# EASY_EDA_File.net
KiCad netlist of a schematic drawn in EasyEDA
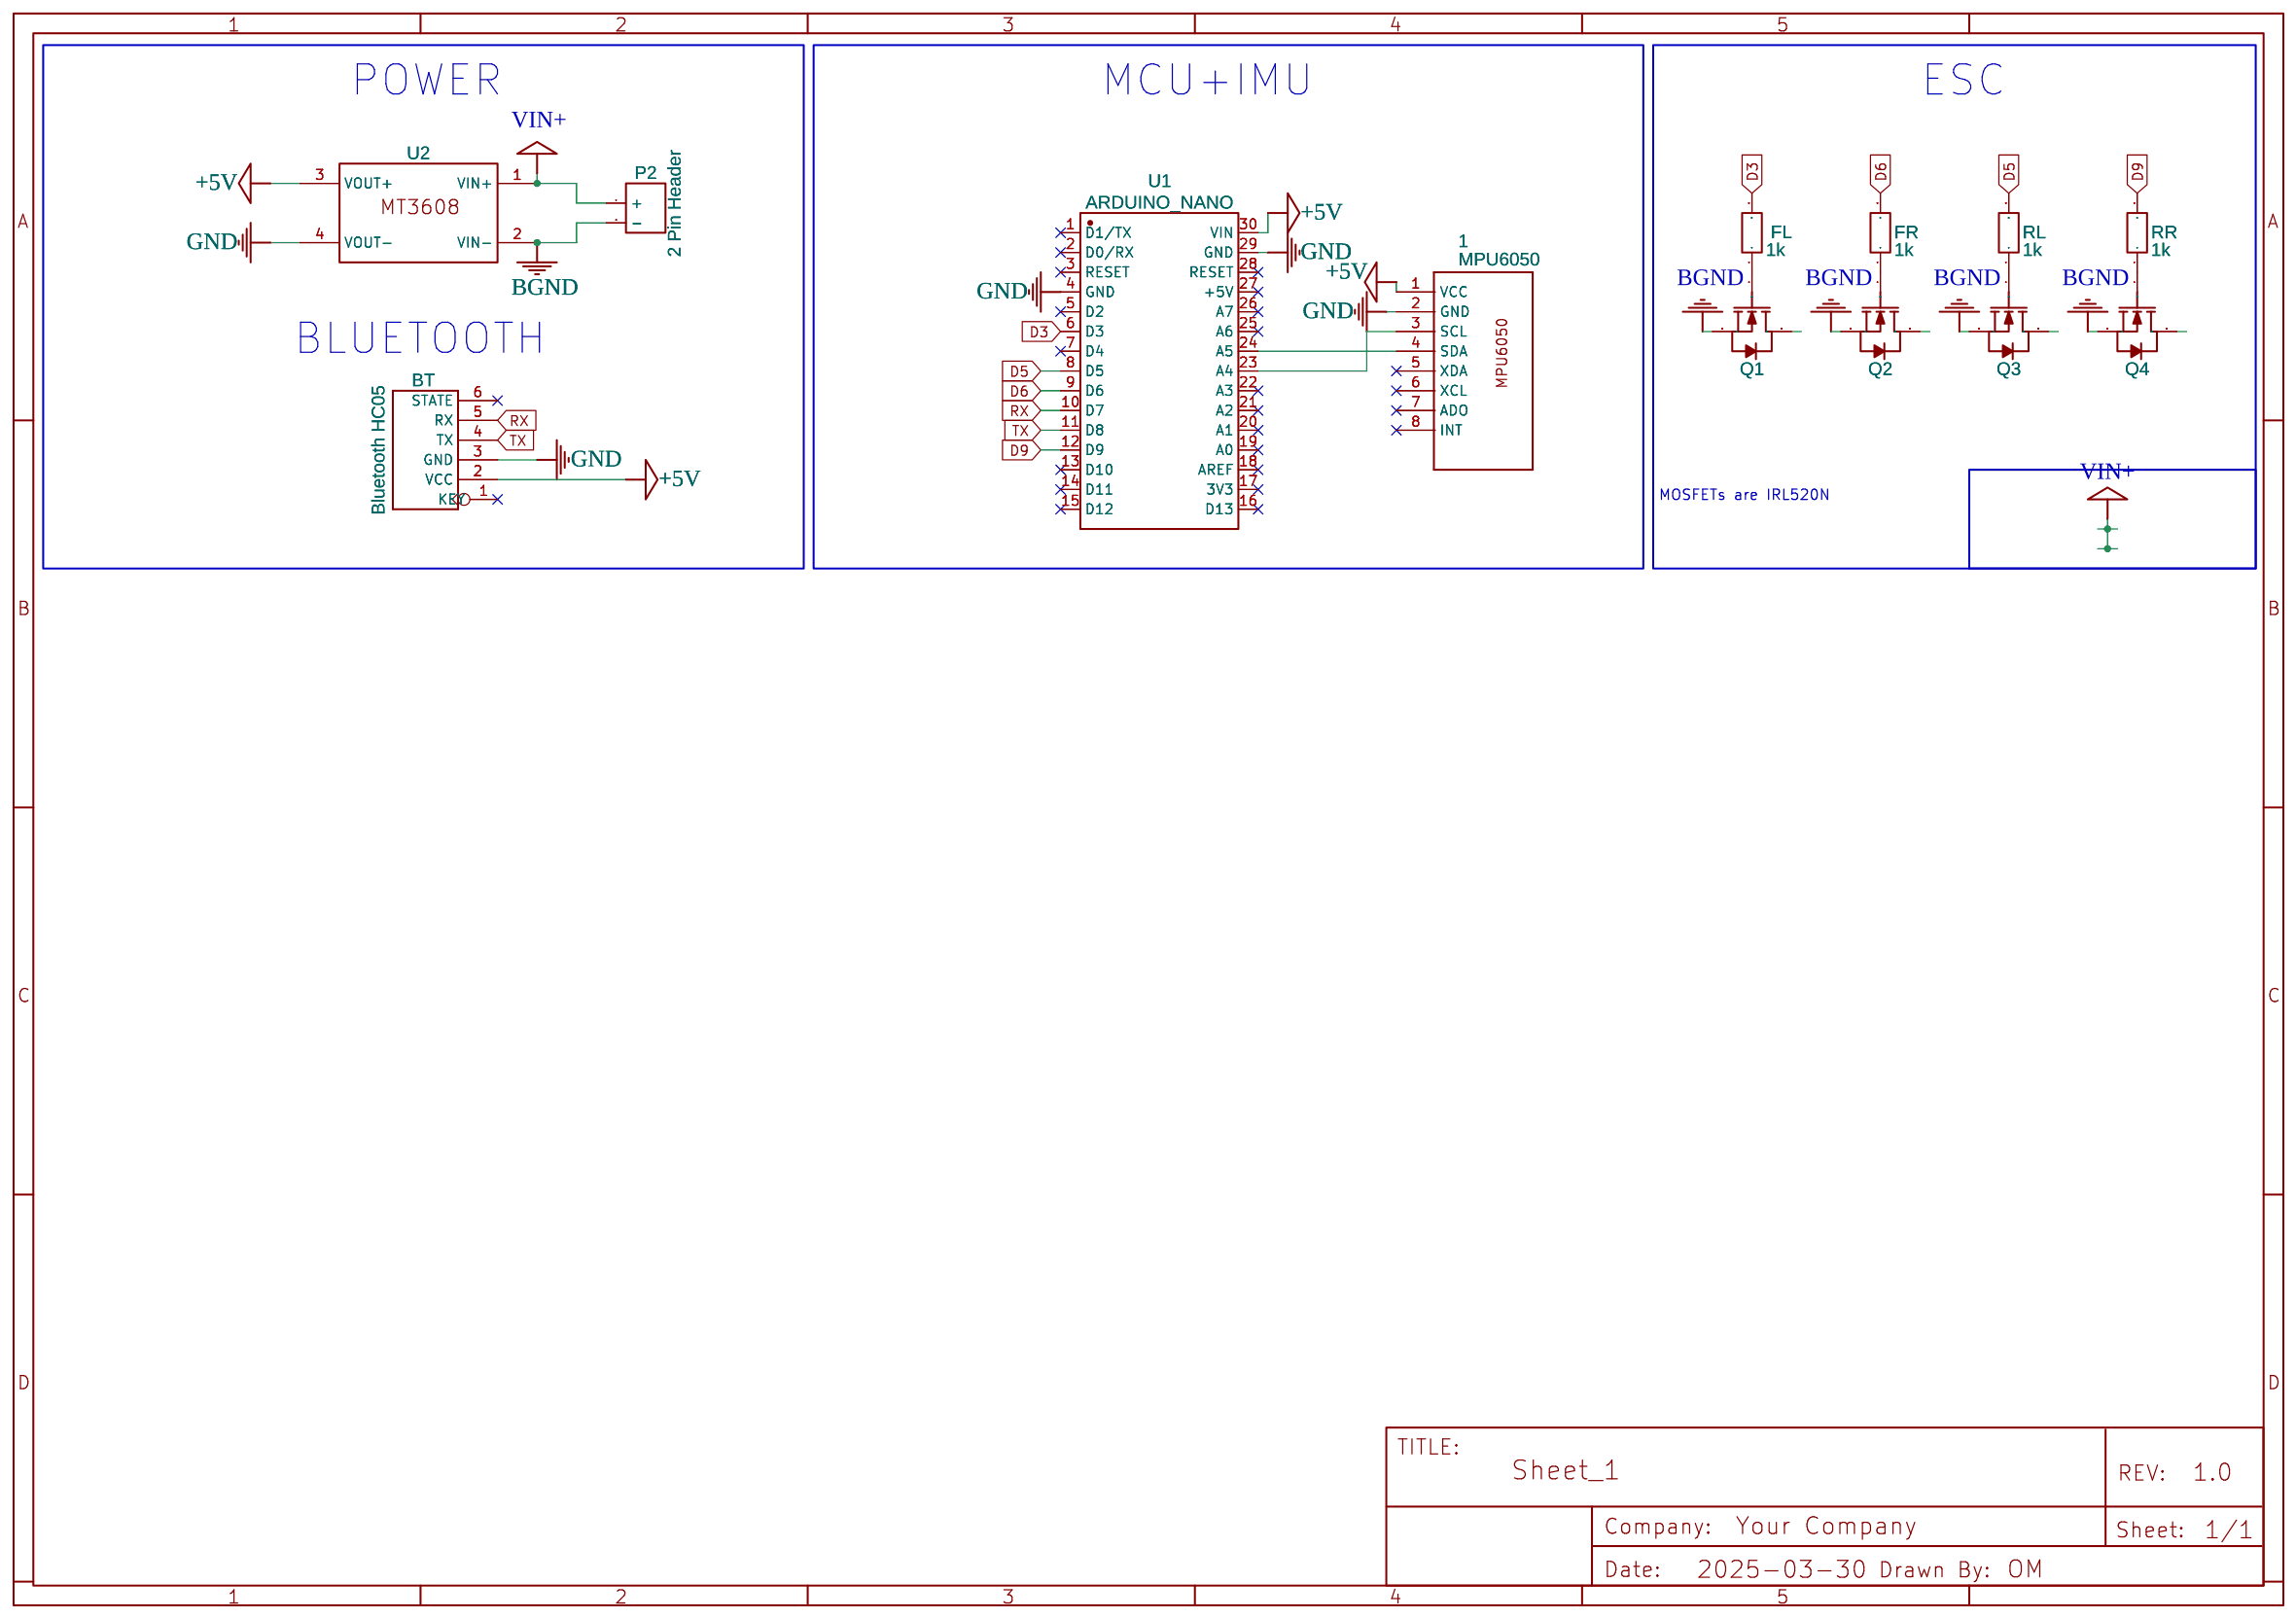
[diagram p0: schematic sheet]

(export (version "E")
  (design (tool "Eeschema 10.0.6"))
  (components
    (comp (ref "1") (value "MPU6050") (libsource (lib "") (part "MPU6050")))
    (comp (ref "BT") (value "Bluetooth HC05") (libsource (lib "") (part "Bluetooth HC05")))
    (comp (ref "FL") (value "1k") (libsource (lib "") (part "R_1206_EU_2")))
    (comp (ref "FR") (value "1k") (libsource (lib "") (part "R_1206_EU_3")))
    (comp (ref "P2")
      (value "2 Pin Header")
      (fields
        (field (name "Manufacturer Part") "Female headerHDR1X8-2.54")
        (field (name "Manufacturer") "BOOMELE")
      )
      (libsource (lib "") (part "HEADER PAD 2X"))
    )
    (comp (ref "Q1")
      (value "IRL520NPBF")
      (fields (field (name "Manufacturer") "Infineon(英飞凌)"))
      (libsource (lib "") (part "IRL520NPBF"))
    )
    (comp (ref "Q2")
      (value "IRL520NPBF")
      (fields (field (name "Manufacturer") "Infineon(英飞凌)"))
      (libsource (lib "") (part "IRL520NPBF"))
    )
    (comp (ref "Q3")
      (value "IRL520NPBF")
      (fields (field (name "Manufacturer") "Infineon(英飞凌)"))
      (libsource (lib "") (part "IRL520NPBF"))
    )
    (comp (ref "Q4")
      (value "IRL520NPBF")
      (fields (field (name "Manufacturer") "Infineon(英飞凌)"))
      (libsource (lib "") (part "IRL520NPBF"))
    )
    (comp (ref "RL") (value "1k") (libsource (lib "") (part "R_1206_EU_1")))
    (comp (ref "RR") (value "1k") (libsource (lib "") (part "R_1206_EU")))
    (comp (ref "U1") (value "ARDUINO_NANO") (libsource (lib "") (part "ARDUINO_NANO")))
    (comp (ref "U2") (value "MT3608") (libsource (lib "") (part "MT3608BOARD")))
  )
  (nets
    (net (code "1") (name "+5V") (class "Default")
      (node (ref "1") (pin "1") (pinfunction "VCC_1") (pintype "bidirectional"))
      (node (ref "BT") (pin "2") (pinfunction "VCC_2") (pintype "unspecified"))
      (node (ref "U1") (pin "30") (pinfunction "VIN_30") (pintype "unspecified"))
      (node (ref "U2") (pin "3") (pinfunction "VOUT+_3") (pintype "unspecified"))
    )
    (net (code "2") (name "BGND") (class "Default")
      (node (ref "P2") (pin "2") (pinfunction "-_2") (pintype "unspecified"))
      (node (ref "Q1") (pin "3") (pinfunction "S_3") (pintype "unspecified"))
      (node (ref "Q2") (pin "3") (pinfunction "S_3") (pintype "unspecified"))
      (node (ref "Q3") (pin "3") (pinfunction "S_3") (pintype "unspecified"))
      (node (ref "Q4") (pin "3") (pinfunction "S_3") (pintype "unspecified"))
      (node (ref "U2") (pin "2") (pinfunction "VIN-_2") (pintype "unspecified"))
    )
    (net (code "3") (name "D3") (class "Default")
      (node (ref "FL") (pin "2") (pinfunction "2_2") (pintype "unspecified"))
      (node (ref "U1") (pin "6") (pinfunction "D3_6") (pintype "unspecified"))
    )
    (net (code "4") (name "D5") (class "Default")
      (node (ref "RL") (pin "2") (pinfunction "2_2") (pintype "unspecified"))
      (node (ref "U1") (pin "8") (pinfunction "D5_8") (pintype "unspecified"))
    )
    (net (code "5") (name "D6") (class "Default")
      (node (ref "FR") (pin "2") (pinfunction "2_2") (pintype "unspecified"))
      (node (ref "U1") (pin "9") (pinfunction "D6_9") (pintype "unspecified"))
    )
    (net (code "6") (name "D9") (class "Default")
      (node (ref "RR") (pin "2") (pinfunction "2_2") (pintype "unspecified"))
      (node (ref "U1") (pin "12") (pinfunction "D9_12") (pintype "unspecified"))
    )
    (net (code "7") (name "GND") (class "Default")
      (node (ref "1") (pin "2") (pinfunction "GND_2") (pintype "bidirectional"))
      (node (ref "BT") (pin "3") (pinfunction "GND_3") (pintype "unspecified"))
      (node (ref "U1") (pin "29") (pinfunction "GND_29") (pintype "unspecified"))
      (node (ref "U1") (pin "4") (pinfunction "GND_4") (pintype "unspecified"))
      (node (ref "U2") (pin "4") (pinfunction "VOUT-_4") (pintype "unspecified"))
    )
    (net (code "8") (name "Net-(1-SCL)") (class "Default")
      (node (ref "1") (pin "3") (pinfunction "SCL_3") (pintype "bidirectional"))
      (node (ref "U1") (pin "23") (pinfunction "A4_23") (pintype "unspecified"))
    )
    (net (code "9") (name "Net-(1-SDA)") (class "Default")
      (node (ref "1") (pin "4") (pinfunction "SDA_4") (pintype "bidirectional"))
      (node (ref "U1") (pin "24") (pinfunction "A5_24") (pintype "unspecified"))
    )
    (net (code "10") (name "Net-(Q1-G)") (class "Default")
      (node (ref "FL") (pin "1") (pinfunction "1_1") (pintype "unspecified"))
      (node (ref "Q1") (pin "1") (pinfunction "G_1") (pintype "unspecified"))
    )
    (net (code "11") (name "Net-(Q2-G)") (class "Default")
      (node (ref "FR") (pin "1") (pinfunction "1_1") (pintype "unspecified"))
      (node (ref "Q2") (pin "1") (pinfunction "G_1") (pintype "unspecified"))
    )
    (net (code "12") (name "Net-(Q3-G)") (class "Default")
      (node (ref "Q3") (pin "1") (pinfunction "G_1") (pintype "unspecified"))
      (node (ref "RL") (pin "1") (pinfunction "1_1") (pintype "unspecified"))
    )
    (net (code "13") (name "Net-(Q4-G)") (class "Default")
      (node (ref "Q4") (pin "1") (pinfunction "G_1") (pintype "unspecified"))
      (node (ref "RR") (pin "1") (pinfunction "1_1") (pintype "unspecified"))
    )
    (net (code "14") (name "RX") (class "Default")
      (node (ref "BT") (pin "5") (pinfunction "RX_5") (pintype "unspecified"))
      (node (ref "U1") (pin "10") (pinfunction "D7_10") (pintype "unspecified"))
    )
    (net (code "15") (name "TX") (class "Default")
      (node (ref "BT") (pin "4") (pinfunction "TX_4") (pintype "unspecified"))
      (node (ref "U1") (pin "11") (pinfunction "D8_11") (pintype "unspecified"))
    )
    (net (code "16") (name "VIN+") (class "Default")
      (node (ref "P2") (pin "1") (pinfunction "+_1") (pintype "unspecified"))
      (node (ref "U2") (pin "1") (pinfunction "VIN+_1") (pintype "unspecified"))
    )
    (net (code "17") (name "unconnected-(1-ADO-Pad7)") (class "Default")
      (node (ref "1") (pin "7") (pinfunction "ADO_7") (pintype "bidirectional+no_connect"))
    )
    (net (code "18") (name "unconnected-(1-INT-Pad8)") (class "Default")
      (node (ref "1") (pin "8") (pinfunction "INT_8") (pintype "bidirectional+no_connect"))
    )
    (net (code "19") (name "unconnected-(1-XCL-Pad6)") (class "Default")
      (node (ref "1") (pin "6") (pinfunction "XCL_6") (pintype "bidirectional+no_connect"))
    )
    (net (code "20") (name "unconnected-(1-XDA-Pad5)") (class "Default")
      (node (ref "1") (pin "5") (pinfunction "XDA_5") (pintype "bidirectional+no_connect"))
    )
    (net (code "21") (name "unconnected-(BT-KEY-Pad1)") (class "Default")
      (node (ref "BT") (pin "1") (pinfunction "KEY_1") (pintype "unspecified+no_connect"))
    )
    (net (code "22") (name "unconnected-(BT-STATE-Pad6)") (class "Default")
      (node (ref "BT") (pin "6") (pinfunction "STATE_6") (pintype "unspecified+no_connect"))
    )
    (net (code "23") (name "unconnected-(Q1-D-Pad2)") (class "Default")
      (node (ref "Q1") (pin "2") (pinfunction "D_2") (pintype "unspecified"))
    )
    (net (code "24") (name "unconnected-(Q2-D-Pad2)") (class "Default")
      (node (ref "Q2") (pin "2") (pinfunction "D_2") (pintype "unspecified"))
    )
    (net (code "25") (name "unconnected-(Q3-D-Pad2)") (class "Default")
      (node (ref "Q3") (pin "2") (pinfunction "D_2") (pintype "unspecified"))
    )
    (net (code "26") (name "unconnected-(Q4-D-Pad2)") (class "Default")
      (node (ref "Q4") (pin "2") (pinfunction "D_2") (pintype "unspecified"))
    )
    (net (code "27") (name "unconnected-(U1-+5V-Pad27)") (class "Default")
      (node (ref "U1") (pin "27") (pinfunction "+5V_27") (pintype "unspecified+no_connect"))
    )
    (net (code "28") (name "unconnected-(U1-3V3-Pad17)") (class "Default")
      (node (ref "U1") (pin "17") (pinfunction "3V3_17") (pintype "unspecified+no_connect"))
    )
    (net (code "29") (name "unconnected-(U1-A0-Pad19)") (class "Default")
      (node (ref "U1") (pin "19") (pinfunction "A0_19") (pintype "unspecified+no_connect"))
    )
    (net (code "30") (name "unconnected-(U1-A1-Pad20)") (class "Default")
      (node (ref "U1") (pin "20") (pinfunction "A1_20") (pintype "unspecified+no_connect"))
    )
    (net (code "31") (name "unconnected-(U1-A2-Pad21)") (class "Default")
      (node (ref "U1") (pin "21") (pinfunction "A2_21") (pintype "unspecified+no_connect"))
    )
    (net (code "32") (name "unconnected-(U1-A3-Pad22)") (class "Default")
      (node (ref "U1") (pin "22") (pinfunction "A3_22") (pintype "unspecified+no_connect"))
    )
    (net (code "33") (name "unconnected-(U1-A6-Pad25)") (class "Default")
      (node (ref "U1") (pin "25") (pinfunction "A6_25") (pintype "unspecified+no_connect"))
    )
    (net (code "34") (name "unconnected-(U1-A7-Pad26)") (class "Default")
      (node (ref "U1") (pin "26") (pinfunction "A7_26") (pintype "unspecified+no_connect"))
    )
    (net (code "35") (name "unconnected-(U1-AREF-Pad18)") (class "Default")
      (node (ref "U1") (pin "18") (pinfunction "AREF_18") (pintype "unspecified+no_connect"))
    )
    (net (code "36") (name "unconnected-(U1-D0{slash}RX-Pad2)") (class "Default")
      (node (ref "U1") (pin "2") (pinfunction "D0/RX_2") (pintype "unspecified+no_connect"))
    )
    (net (code "37") (name "unconnected-(U1-D1{slash}TX-Pad1)") (class "Default")
      (node (ref "U1") (pin "1") (pinfunction "D1/TX_1") (pintype "unspecified+no_connect"))
    )
    (net (code "38") (name "unconnected-(U1-D2-Pad5)") (class "Default")
      (node (ref "U1") (pin "5") (pinfunction "D2_5") (pintype "unspecified+no_connect"))
    )
    (net (code "39") (name "unconnected-(U1-D4-Pad7)") (class "Default")
      (node (ref "U1") (pin "7") (pinfunction "D4_7") (pintype "unspecified+no_connect"))
    )
    (net (code "40") (name "unconnected-(U1-D10-Pad13)") (class "Default")
      (node (ref "U1") (pin "13") (pinfunction "D10_13") (pintype "unspecified+no_connect"))
    )
    (net (code "41") (name "unconnected-(U1-D11-Pad14)") (class "Default")
      (node (ref "U1") (pin "14") (pinfunction "D11_14") (pintype "unspecified+no_connect"))
    )
    (net (code "42") (name "unconnected-(U1-D12-Pad15)") (class "Default")
      (node (ref "U1") (pin "15") (pinfunction "D12_15") (pintype "unspecified+no_connect"))
    )
    (net (code "43") (name "unconnected-(U1-D13-Pad16)") (class "Default")
      (node (ref "U1") (pin "16") (pinfunction "D13_16") (pintype "unspecified+no_connect"))
    )
    (net (code "44") (name "unconnected-(U1-RESET-Pad3)") (class "Default")
      (node (ref "U1") (pin "3") (pinfunction "RESET_3") (pintype "unspecified+no_connect"))
    )
    (net (code "45") (name "unconnected-(U1-RESET-Pad28)") (class "Default")
      (node (ref "U1") (pin "28") (pinfunction "RESET_28") (pintype "unspecified+no_connect"))
    )
  )
)
